# main-DESKTOP-L9L0IAD.net
KiCad netlist of a schematic drawn in Altium Designer
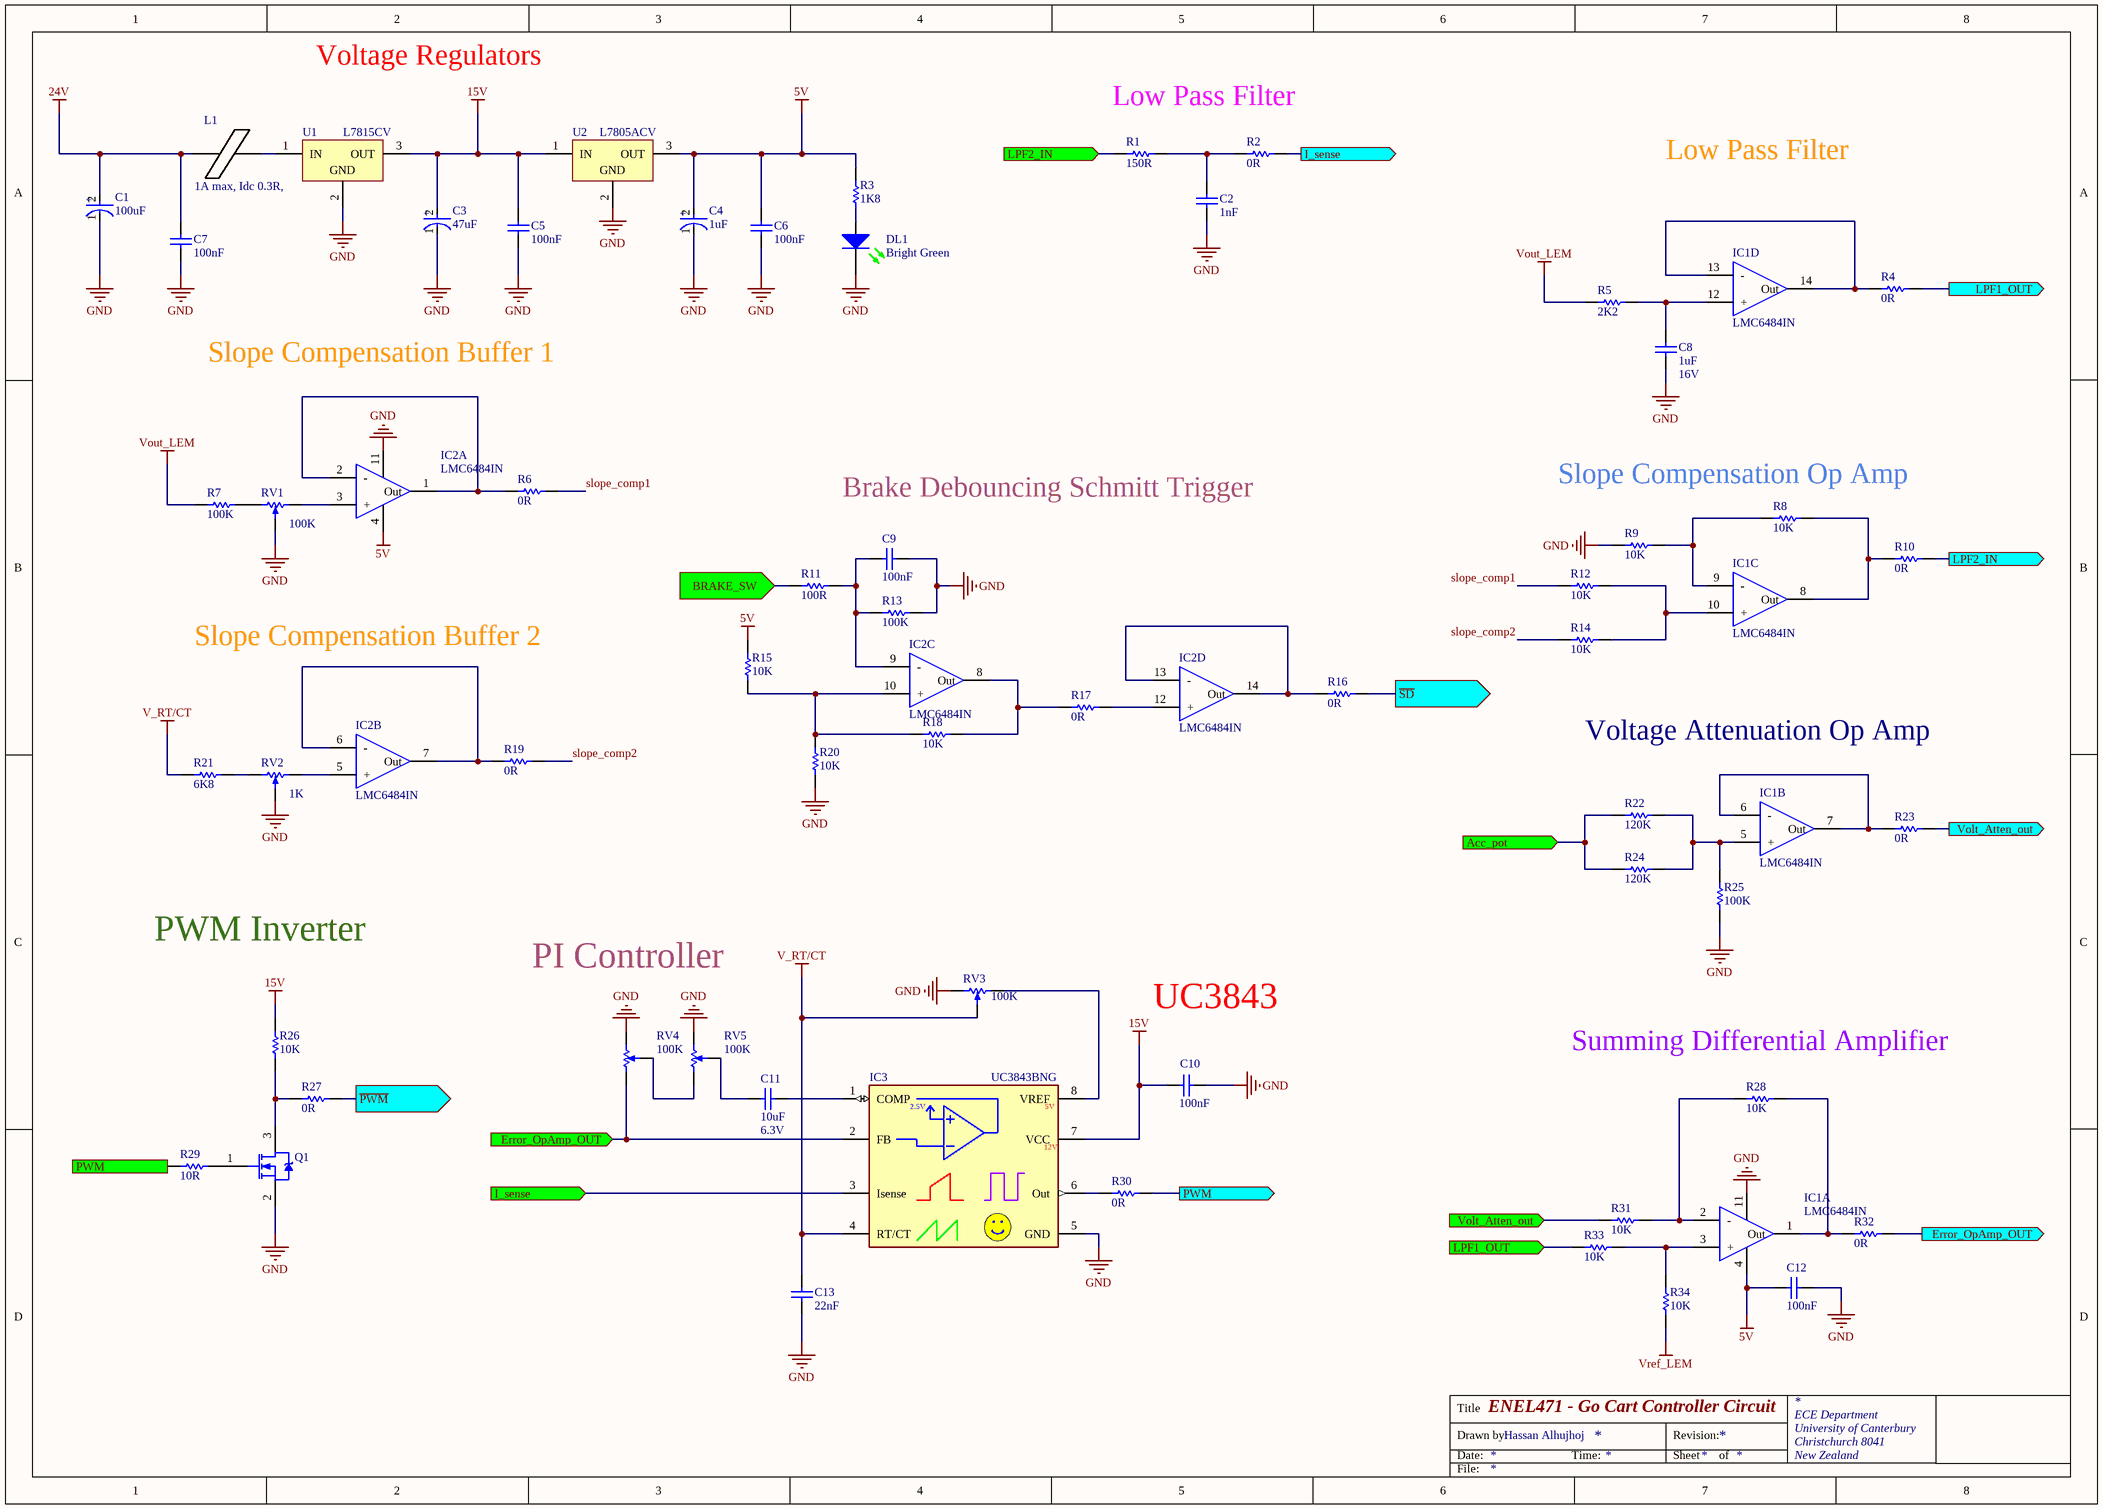
[diagram p0: main-DESKTOP-L9L0IAD.SchDoc]

(export (version "E")
  (design (tool "Eeschema 10.0.6"))
  (components
    (comp (ref "C1")
      (value "100uF")
      (footprint "FP-ESLGM-MFG")
      (description "CAP ALUM 100UF 20% 50V THRU HOLE. Part Number: ESL107M050AGMAA. Dia: 8mm.")
      (fields
        (field (name "TOLERANCE") "20%")
        (field (name "OCTOPART") "https://octopart.com/esl107m050agmaa-kemet-84758890")
      )
      (libsource (lib "Altium Content Vault") (part "a00bbbee19879c290e62620ae7e47b1"))
    )
    (comp (ref "C2")
      (value "1nF")
      (footprint "CAPC1608L")
      (description "CAP CER 1nF X7R +-10% 50V 0603")
      (libsource (lib "ECE AD19Components_19V1") (part "CC_1nF_0603"))
    )
    (comp (ref "C3")
      (value "47uF")
      (footprint "FP-ESLE3-MFG")
      (description "CAP ALUM 10UF 20% 100V THRU HOLE. Part Number: ESL106M100AE3AA. Dia: 6.3mm.")
      (fields (field (name "TOLERANCE") "20%") (field (name "MANUFACTURER PART NUMBER") "ESL106M100AE3AA"))
      (libsource (lib "Altium Content Vault") (part "cf48714ba7e38822c1575c7ec0b6d1f"))
    )
    (comp (ref "C4")
      (value "1uF")
      (footprint "FP-UPW1E220MDD-MFG")
      (description "CAP ALUM 22UF 20% 25V RADIAL. Part Number: UPW1E220MDD. Dia: 5mm.")
      (fields
        (field (name "OCTOPART") "https://octopart.com/upw1e220mdd-nichicon-202818")
        (field (name "TOLERANCE") "20%")
      )
      (libsource (lib "Altium Content Vault") (part "cf48714ba7e38822c1575c7ec0b6d1f"))
    )
    (comp (ref "C5")
      (value "100nF")
      (footprint "CAPC1608L")
      (description "CAP CER 100nF X7R +-10% 50V 0603")
      (libsource (lib "ECE AD19Components_19V1") (part "CC_100nF_0603"))
    )
    (comp (ref "C6")
      (value "100nF")
      (footprint "CAPC1608L")
      (description "CAP CER 100nF X7R +-10% 50V 0603")
      (libsource (lib "ECE AD19Components_19V1") (part "CC_100nF_0603"))
    )
    (comp (ref "C7")
      (value "100nF")
      (footprint "CAPC1608L")
      (description "CAP CER 100nF X7R +-10% 50V 0603")
      (libsource (lib "ECE AD19Components_19V1") (part "CC_100nF_0603"))
    )
    (comp (ref "C8")
      (value "1uF")
      (footprint "CAPC1608L")
      (description "CAP CER 1uF Y5V -20% +80% 16V 0603")
      (fields (field (name "MAX VOLTAGE") "16V"))
      (libsource (lib "ECE AD19Components_19V1") (part "CC_1uF_0603"))
    )
    (comp (ref "C9")
      (value "100nF")
      (footprint "CAPC1608L")
      (description "CAP CER 100nF X7R +-10% 50V 0603")
      (libsource (lib "ECE AD19Components_19V1") (part "CC_100nF_0603"))
    )
    (comp (ref "C10")
      (value "100nF")
      (footprint "CAPC1608L")
      (description "CAP CER 100nF X7R +-10% 50V 0603")
      (libsource (lib "ECE AD19Components_19V1") (part "CC_100nF_0603"))
    )
    (comp (ref "C11")
      (value "10uF")
      (footprint "CAPC1608L")
      (description "CAP CER 10UF X5R +-20% 6V3 0603")
      (fields (field (name "VOLTAGE - RATED") "6.3V"))
      (libsource (lib "ECE AD19Components_19V1") (part "CC_10uF_0603"))
    )
    (comp (ref "C12")
      (value "100nF")
      (footprint "CAPC1608L")
      (description "CAP CER 100nF X7R +-10% 50V 0603")
      (libsource (lib "ECE AD19Components_19V1") (part "CC_100nF_0603"))
    )
    (comp (ref "C13")
      (value "22nF")
      (footprint "CAPC1608L")
      (description "CAP CER 22nF X7R +-10% 50V 0603")
      (libsource (lib "ECE AD19Components_19V1") (part "CC_22nF_0603"))
    )
    (comp (ref "DL1")
      (value "Bright Green")
      (footprint "WL-SMCW0603")
      (description "LED Bright Green 40mcd 0603 SMD")
      (fields
        (field (name "MANUFACTURER") "WURTH ELEKTRONIK")
        (field (name "MANUFACTURER PART NUMBER") "150060VS75000")
        (field (name "LED COLOUR") "Bright Green")
      )
      (libsource (lib "ECE AD19Components_19V1") (part "DL_150060VS75000"))
    )
    (comp (ref "IC1")
      (value "LMC6484IN")
      (footprint "SamacSys:DIP794W56P254L1905H533Q14N")
      (description "Integrated Circuit")
      (fields (field (name "MOUSER PART NUMBER") "926-LMC6484IN"))
      (libsource (lib "SamacSys") (part "LMC6484IN"))
    )
    (comp (ref "IC2")
      (value "LMC6484IN")
      (footprint "SamacSys:DIP794W56P254L1905H533Q14N")
      (description "Integrated Circuit")
      (fields (field (name "MOUSER PART NUMBER") "926-LMC6484IN"))
      (libsource (lib "SamacSys") (part "LMC6484IN"))
    )
    (comp (ref "IC3")
      (value "UC3843BNG")
      (footprint "SamacSys:DIP794W56P254L959H533Q8B")
      (description "Integrated Circuit")
      (fields (field (name "MOUSER PART NUMBER") "863-UC3843BNG"))
      (libsource (lib "SamacSys") (part "UC3843BNG"))
    )
    (comp (ref "L1")
      (value "1A max, Idc 0.3R,")
      (footprint "INDC3216L")
      (description "Ferrite Bead, Rdc 0.3R, Z100MHZ 600R, Imax 1A, SMD 1206")
      (fields
        (field (name "MANUFACTURER") "FAIR-RITE")
        (field (name "MANUFACTURER PART NUMBER") "2512066017Y1")
      )
      (libsource (lib "ECE AD19Components_19V1") (part "IN_Ferrite-Bead"))
    )
    (comp (ref "Q1")
      (value "ZXM61N02FTA")
      (footprint "SOT23_L")
      (description "MOSFET N-CH 20V 1.7A SOT23-3")
      (fields (field (name "MANUFACTURER") "Diodes Inc"))
      (libsource (lib "ECE AD19Components_19V1") (part "TM_ZXM61N02FTA"))
    )
    (comp (ref "R1")
      (value "150R")
      (footprint "RESC1608L")
      (description "RES 150 OHM 1/10W 5% 0603 SMD")
      (libsource (lib "ECE AD19Components_19V1") (part "RS_150R"))
    )
    (comp (ref "R2")
      (value "0R")
      (footprint "RESC1608L")
      (description "RES 0.0 OHM 1/10W 5% 0603 SMD")
      (libsource (lib "ECE AD19Components_19V1") (part "RS_0R0"))
    )
    (comp (ref "R3")
      (value "1K8")
      (footprint "RESC1608L")
      (description "RES 1.8K OHM 1/10W 5% 0603 SMD")
      (libsource (lib "ECE AD19Components_19V1") (part "RS_1K8"))
    )
    (comp (ref "R4")
      (value "0R")
      (footprint "RESC1608L")
      (description "RES 0.0 OHM 1/10W 5% 0603 SMD")
      (libsource (lib "ECE AD19Components_19V1") (part "RS_0R0"))
    )
    (comp (ref "R5")
      (value "2K2")
      (footprint "RESC1608L")
      (description "RES 2.2K OHM 1/10W 5% 0603 SMD")
      (libsource (lib "ECE AD19Components_19V1") (part "RS_2K2"))
    )
    (comp (ref "R6")
      (value "0R")
      (footprint "RESC1608L")
      (description "RES 0.0 OHM 1/10W 5% 0603 SMD")
      (libsource (lib "ECE AD19Components_19V1") (part "RS_0R0"))
    )
    (comp (ref "R7")
      (value "100K")
      (footprint "RESC1608L")
      (description "RES 100K OHM 1/10W 5% 0603 SMD")
      (libsource (lib "ECE AD19Components_19V1") (part "RS_100K"))
    )
    (comp (ref "R8")
      (value "10K")
      (footprint "RESC1608L")
      (description "RES 10.0K OHM 1/10W 5% 0603 SMD")
      (libsource (lib "ECE AD19Components_19V1") (part "RS_10K"))
    )
    (comp (ref "R9")
      (value "10K")
      (footprint "RESC1608L")
      (description "RES 10.0K OHM 1/10W 5% 0603 SMD")
      (libsource (lib "ECE AD19Components_19V1") (part "RS_10K"))
    )
    (comp (ref "R10")
      (value "0R")
      (footprint "RESC1608L")
      (description "RES 0.0 OHM 1/10W 5% 0603 SMD")
      (libsource (lib "ECE AD19Components_19V1") (part "RS_0R0"))
    )
    (comp (ref "R11")
      (value "100R")
      (footprint "RESC1608L")
      (description "RES 100 OHM 1/10W 5% 0603 SMD")
      (libsource (lib "ECE AD19Components_19V1") (part "RS_100R"))
    )
    (comp (ref "R12")
      (value "10K")
      (footprint "RESC1608L")
      (description "RES 10.0K OHM 1/10W 5% 0603 SMD")
      (libsource (lib "ECE AD19Components_19V1") (part "RS_10K"))
    )
    (comp (ref "R13")
      (value "100K")
      (footprint "RESC1608L")
      (description "RES 100K OHM 1/10W 5% 0603 SMD")
      (libsource (lib "ECE AD19Components_19V1") (part "RS_100K"))
    )
    (comp (ref "R14")
      (value "10K")
      (footprint "RESC1608L")
      (description "RES 10.0K OHM 1/10W 5% 0603 SMD")
      (libsource (lib "ECE AD19Components_19V1") (part "RS_10K"))
    )
    (comp (ref "R15")
      (value "10K")
      (footprint "RESC1608L")
      (description "RES 10.0K OHM 1/10W 5% 0603 SMD")
      (libsource (lib "ECE AD19Components_19V1") (part "RS_10K"))
    )
    (comp (ref "R16")
      (value "0R")
      (footprint "RESC1608L")
      (description "RES 0.0 OHM 1/10W 5% 0603 SMD")
      (libsource (lib "ECE AD19Components_19V1") (part "RS_0R0"))
    )
    (comp (ref "R17")
      (value "0R")
      (footprint "RESC1608L")
      (description "RES 0.0 OHM 1/10W 5% 0603 SMD")
      (libsource (lib "ECE AD19Components_19V1") (part "RS_0R0"))
    )
    (comp (ref "R18")
      (value "10K")
      (footprint "RESC1608L")
      (description "RES 10.0K OHM 1/10W 5% 0603 SMD")
      (libsource (lib "ECE AD19Components_19V1") (part "RS_10K"))
    )
    (comp (ref "R19")
      (value "0R")
      (footprint "RESC1608L")
      (description "RES 0.0 OHM 1/10W 5% 0603 SMD")
      (libsource (lib "ECE AD19Components_19V1") (part "RS_0R0"))
    )
    (comp (ref "R20")
      (value "10K")
      (footprint "RESC1608L")
      (description "RES 10.0K OHM 1/10W 5% 0603 SMD")
      (libsource (lib "ECE AD19Components_19V1") (part "RS_10K"))
    )
    (comp (ref "R21")
      (value "6K8")
      (footprint "RESC1608L")
      (description "RES 6k8 OHM 1/10W 5% 0603 SMD")
      (libsource (lib "ECE AD19Components_19V1") (part "RS_6K8"))
    )
    (comp (ref "R22")
      (value "120K")
      (footprint "RESC1608L")
      (description "RES 120K OHM 1/10W 5% 0603 SMD")
      (libsource (lib "ECE AD19Components_19V1") (part "RS_120K"))
    )
    (comp (ref "R23")
      (value "0R")
      (footprint "RESC1608L")
      (description "RES 0.0 OHM 1/10W 5% 0603 SMD")
      (libsource (lib "ECE AD19Components_19V1") (part "RS_0R0"))
    )
    (comp (ref "R24")
      (value "120K")
      (footprint "RESC1608L")
      (description "RES 120K OHM 1/10W 5% 0603 SMD")
      (libsource (lib "ECE AD19Components_19V1") (part "RS_120K"))
    )
    (comp (ref "R25")
      (value "100K")
      (footprint "RESC1608L")
      (description "RES 100K OHM 1/10W 5% 0603 SMD")
      (libsource (lib "ECE AD19Components_19V1") (part "RS_100K"))
    )
    (comp (ref "R26")
      (value "10K")
      (footprint "RESC1608L")
      (description "RES 10.0K OHM 1/10W 5% 0603 SMD")
      (libsource (lib "ECE AD19Components_19V1") (part "RS_10K"))
    )
    (comp (ref "R27")
      (value "0R")
      (footprint "RESC1608L")
      (description "RES 0.0 OHM 1/10W 5% 0603 SMD")
      (libsource (lib "ECE AD19Components_19V1") (part "RS_0R0"))
    )
    (comp (ref "R28")
      (value "10K")
      (footprint "RESC1608L")
      (description "RES 10.0K OHM 1/10W 5% 0603 SMD")
      (libsource (lib "ECE AD19Components_19V1") (part "RS_10K"))
    )
    (comp (ref "R29")
      (value "10R")
      (footprint "RESC1608L")
      (description "RES 10 OHM 1/10W 5% 0603 SMD")
      (libsource (lib "ECE AD19Components_19V1") (part "RS_10R"))
    )
    (comp (ref "R30")
      (value "0R")
      (footprint "RESC1608L")
      (description "RES 0.0 OHM 1/10W 5% 0603 SMD")
      (libsource (lib "ECE AD19Components_19V1") (part "RS_0R0"))
    )
    (comp (ref "R31")
      (value "10K")
      (footprint "RESC1608L")
      (description "RES 10.0K OHM 1/10W 5% 0603 SMD")
      (libsource (lib "ECE AD19Components_19V1") (part "RS_10K"))
    )
    (comp (ref "R32")
      (value "0R")
      (footprint "RESC1608L")
      (description "RES 0.0 OHM 1/10W 5% 0603 SMD")
      (libsource (lib "ECE AD19Components_19V1") (part "RS_0R0"))
    )
    (comp (ref "R33")
      (value "10K")
      (footprint "RESC1608L")
      (description "RES 10.0K OHM 1/10W 5% 0603 SMD")
      (libsource (lib "ECE AD19Components_19V1") (part "RS_10K"))
    )
    (comp (ref "R34")
      (value "10K")
      (footprint "RESC1608L")
      (description "RES 10.0K OHM 1/10W 5% 0603 SMD")
      (libsource (lib "ECE AD19Components_19V1") (part "RS_10K"))
    )
    (comp (ref "RV1")
      (value "100K")
      (footprint "PVZ2A")
      (description "Trim Pot SMD 100K Murata PVZ2 Series SMD")
      (fields
        (field (name "MANUFACTURER") "MURATA")
        (field (name "MANUFACTURER PART NUMBER") "PVZ2A104C04B00")
      )
      (libsource (lib "ECE AD19Components_19V1") (part "RM_100K"))
    )
    (comp (ref "RV2")
      (value "1K")
      (footprint "PVZ2A")
      (description "Trim Pot SMD 1K Murata PVZ2 Series SMD")
      (fields
        (field (name "MANUFACTURER") "MURATA")
        (field (name "MANUFACTURER PART NUMBER") "PVZ2A102C04B00")
      )
      (libsource (lib "ECE AD19Components_19V1") (part "RM_1K"))
    )
    (comp (ref "RV3")
      (value "100K")
      (footprint "PVZ2A")
      (description "Trim Pot SMD 100K Murata PVZ2 Series SMD")
      (fields
        (field (name "MANUFACTURER") "MURATA")
        (field (name "MANUFACTURER PART NUMBER") "PVZ2A104C04B00")
      )
      (libsource (lib "ECE AD19Components_19V1") (part "RM_100K"))
    )
    (comp (ref "RV4")
      (value "100K")
      (footprint "PVZ2A")
      (description "Trim Pot SMD 100K Murata PVZ2 Series SMD")
      (fields
        (field (name "MANUFACTURER") "MURATA")
        (field (name "MANUFACTURER PART NUMBER") "PVZ2A104C04B00")
      )
      (libsource (lib "ECE AD19Components_19V1") (part "RM_100K"))
    )
    (comp (ref "RV5")
      (value "100K")
      (footprint "PVZ2A")
      (description "Trim Pot SMD 100K Murata PVZ2 Series SMD")
      (fields
        (field (name "MANUFACTURER") "MURATA")
        (field (name "MANUFACTURER PART NUMBER") "PVZ2A104C04B00")
      )
      (libsource (lib "ECE AD19Components_19V1") (part "RM_100K"))
    )
    (comp (ref "U1")
      (value "L7815CV")
      (footprint "TO220")
      (description "Positive Voltage Regulator, 15V, 3-Pin TO-220")
      (libsource (lib "Altium Content Vault") (part "PM-REG-L4940-SIL3"))
    )
    (comp (ref "U2")
      (value "L7805ACV")
      (footprint "TO220")
      (description "Positive Voltage Regulator, 5V, 3-Pin TO-220")
      (libsource (lib "Altium Content Vault") (part "PM-REG-L4940-SIL3"))
    )
  )
  (nets
    (net (code "1") (name "/Acc_pot") (class "Default")
      (node (ref "R22") (pin "2") (pinfunction "2_2") (pintype "passive"))
      (node (ref "R24") (pin "1") (pinfunction "1_1") (pintype "passive"))
    )
    (net (code "2") (name "/BRAKE_SW") (class "Default")
      (node (ref "R11") (pin "1") (pinfunction "1_1") (pintype "passive"))
    )
    (net (code "3") (name "/Error_OpAmp_OUT") (class "Default")
      (node (ref "IC3") (pin "2") (pinfunction "FB_2") (pintype "passive"))
      (node (ref "R32") (pin "2") (pinfunction "2_2") (pintype "passive"))
      (node (ref "RV4") (pin "3") (pinfunction "-_3") (pintype "passive"))
    )
    (net (code "4") (name "/I_sense") (class "Default")
      (node (ref "IC3") (pin "3") (pinfunction "Isense_3") (pintype "passive"))
      (node (ref "R2") (pin "2") (pinfunction "2_2") (pintype "passive"))
    )
    (net (code "5") (name "/LPF1_OUT") (class "Default")
      (node (ref "R33") (pin "1") (pinfunction "1_1") (pintype "passive"))
      (node (ref "R4") (pin "2") (pinfunction "2_2") (pintype "passive"))
    )
    (net (code "6") (name "/LPF2_IN") (class "Default")
      (node (ref "R1") (pin "1") (pinfunction "1_1") (pintype "passive"))
      (node (ref "R10") (pin "2") (pinfunction "2_2") (pintype "passive"))
    )
    (net (code "7") (name "/PWM") (class "Default")
      (node (ref "R29") (pin "1") (pinfunction "1_1") (pintype "passive"))
      (node (ref "R30") (pin "2") (pinfunction "2_2") (pintype "passive"))
    )
    (net (code "8") (name "/Volt_Atten_out") (class "Default")
      (node (ref "R23") (pin "2") (pinfunction "2_2") (pintype "passive"))
      (node (ref "R31") (pin "1") (pinfunction "1_1") (pintype "passive"))
    )
    (net (code "9") (name "/slope_comp1") (class "Default")
      (node (ref "R12") (pin "1") (pinfunction "1_1") (pintype "passive"))
      (node (ref "R6") (pin "2") (pinfunction "2_2") (pintype "passive"))
    )
    (net (code "10") (name "/slope_comp2") (class "Default")
      (node (ref "R14") (pin "1") (pinfunction "1_1") (pintype "passive"))
      (node (ref "R19") (pin "2") (pinfunction "2_2") (pintype "passive"))
    )
    (net (code "11") (name "/~{PWM}") (class "Default")
      (node (ref "R27") (pin "2") (pinfunction "2_2") (pintype "passive"))
    )
    (net (code "12") (name "/~{SD}") (class "Default")
      (node (ref "R16") (pin "2") (pinfunction "2_2") (pintype "passive"))
    )
    (net (code "13") (name "5V") (class "Default")
      (node (ref "C12") (pin "1") (pinfunction "1_1") (pintype "passive"))
      (node (ref "C4") (pin "2") (pinfunction "A_2") (pintype "passive"))
      (node (ref "C6") (pin "1") (pinfunction "1_1") (pintype "passive"))
      (node (ref "IC1") (pin "4") (pinfunction "Vcc_4") (pintype "power_in"))
      (node (ref "IC2") (pin "4") (pinfunction "Vcc_4") (pintype "power_in"))
      (node (ref "R15") (pin "2") (pinfunction "2_2") (pintype "passive"))
      (node (ref "R3") (pin "1") (pinfunction "1_1") (pintype "passive"))
      (node (ref "U2") (pin "3") (pinfunction "OUT_3") (pintype "power_in"))
    )
    (net (code "14") (name "15V") (class "Default")
      (node (ref "C10") (pin "1") (pinfunction "1_1") (pintype "passive"))
      (node (ref "C3") (pin "2") (pinfunction "A_2") (pintype "passive"))
      (node (ref "C5") (pin "1") (pinfunction "1_1") (pintype "passive"))
      (node (ref "IC3") (pin "7") (pinfunction "VCC_7") (pintype "power_in"))
      (node (ref "R26") (pin "2") (pinfunction "2_2") (pintype "passive"))
      (node (ref "U1") (pin "3") (pinfunction "OUT_3") (pintype "power_in"))
      (node (ref "U2") (pin "1") (pinfunction "IN_1") (pintype "power_in"))
    )
    (net (code "15") (name "24V") (class "Default")
      (node (ref "C1") (pin "2") (pinfunction "A_2") (pintype "passive"))
      (node (ref "C7") (pin "1") (pinfunction "1_1") (pintype "passive"))
      (node (ref "L1") (pin "1") (pinfunction "1_1") (pintype "passive"))
    )
    (net (code "16") (name "GND") (class "Default")
      (node (ref "C1") (pin "1") (pinfunction "C_1") (pintype "passive"))
      (node (ref "C10") (pin "2") (pinfunction "2_2") (pintype "passive"))
      (node (ref "C12") (pin "2") (pinfunction "2_2") (pintype "passive"))
      (node (ref "C13") (pin "2") (pinfunction "2_2") (pintype "passive"))
      (node (ref "C2") (pin "1") (pinfunction "1_1") (pintype "passive"))
      (node (ref "C3") (pin "1") (pinfunction "C_1") (pintype "passive"))
      (node (ref "C4") (pin "1") (pinfunction "C_1") (pintype "passive"))
      (node (ref "C5") (pin "2") (pinfunction "2_2") (pintype "passive"))
      (node (ref "C6") (pin "2") (pinfunction "2_2") (pintype "passive"))
      (node (ref "C7") (pin "2") (pinfunction "2_2") (pintype "passive"))
      (node (ref "C8") (pin "1") (pinfunction "1_1") (pintype "passive"))
      (node (ref "C9") (pin "2") (pinfunction "2_2") (pintype "passive"))
      (node (ref "DL1") (pin "1") (pinfunction "K_1") (pintype "passive"))
      (node (ref "IC1") (pin "11") (pinfunction "-Vcc_11") (pintype "power_in"))
      (node (ref "IC2") (pin "11") (pinfunction "-Vcc_11") (pintype "power_in"))
      (node (ref "IC3") (pin "5") (pinfunction "GND_5") (pintype "power_in"))
      (node (ref "Q1") (pin "2") (pinfunction "2_2") (pintype "passive"))
      (node (ref "R13") (pin "2") (pinfunction "2_2") (pintype "passive"))
      (node (ref "R20") (pin "1") (pinfunction "1_1") (pintype "passive"))
      (node (ref "R25") (pin "1") (pinfunction "1_1") (pintype "passive"))
      (node (ref "R9") (pin "1") (pinfunction "1_1") (pintype "passive"))
      (node (ref "RV1") (pin "2") (pinfunction "W_2") (pintype "passive"))
      (node (ref "RV2") (pin "2") (pinfunction "W_2") (pintype "passive"))
      (node (ref "RV3") (pin "3") (pinfunction "-_3") (pintype "passive"))
      (node (ref "RV4") (pin "1") (pinfunction "1_1") (pintype "passive"))
      (node (ref "RV5") (pin "1") (pinfunction "1_1") (pintype "passive"))
      (node (ref "U1") (pin "2") (pinfunction "GND_2") (pintype "power_in"))
      (node (ref "U2") (pin "2") (pinfunction "GND_2") (pintype "power_in"))
    )
    (net (code "17") (name "Net-(C2-Pad2)") (class "Default")
      (node (ref "C2") (pin "2") (pinfunction "2_2") (pintype "passive"))
      (node (ref "R1") (pin "2") (pinfunction "2_2") (pintype "passive"))
      (node (ref "R2") (pin "1") (pinfunction "1_1") (pintype "passive"))
    )
    (net (code "18") (name "Net-(DL1-A)") (class "Default")
      (node (ref "DL1") (pin "2") (pinfunction "A_2") (pintype "passive"))
      (node (ref "R3") (pin "2") (pinfunction "2_2") (pintype "passive"))
    )
    (net (code "19") (name "Net-(IC1A-+)") (class "Default")
      (node (ref "IC1") (pin "3") (pinfunction "+_3") (pintype "passive"))
      (node (ref "R33") (pin "2") (pinfunction "2_2") (pintype "passive"))
      (node (ref "R34") (pin "2") (pinfunction "2_2") (pintype "passive"))
    )
    (net (code "20") (name "Net-(IC1A--)") (class "Default")
      (node (ref "IC1") (pin "2") (pinfunction "-_2") (pintype "passive"))
      (node (ref "R28") (pin "1") (pinfunction "1_1") (pintype "passive"))
      (node (ref "R31") (pin "2") (pinfunction "2_2") (pintype "passive"))
    )
    (net (code "21") (name "Net-(IC1A-Out)") (class "Default")
      (node (ref "IC1") (pin "1") (pinfunction "Out_1") (pintype "passive"))
      (node (ref "R28") (pin "2") (pinfunction "2_2") (pintype "passive"))
      (node (ref "R32") (pin "1") (pinfunction "1_1") (pintype "passive"))
    )
    (net (code "22") (name "Net-(IC1B-+)") (class "Default")
      (node (ref "IC1") (pin "5") (pinfunction "+_5") (pintype "passive"))
      (node (ref "R22") (pin "1") (pinfunction "1_1") (pintype "passive"))
      (node (ref "R24") (pin "2") (pinfunction "2_2") (pintype "passive"))
      (node (ref "R25") (pin "2") (pinfunction "2_2") (pintype "passive"))
    )
    (net (code "23") (name "Net-(IC1B--)") (class "Default")
      (node (ref "IC1") (pin "6") (pinfunction "-_6") (pintype "passive"))
      (node (ref "IC1") (pin "7") (pinfunction "Out_7") (pintype "passive"))
      (node (ref "R23") (pin "1") (pinfunction "1_1") (pintype "passive"))
    )
    (net (code "24") (name "Net-(IC1C-+)") (class "Default")
      (node (ref "IC1") (pin "10") (pinfunction "+_10") (pintype "passive"))
      (node (ref "R12") (pin "2") (pinfunction "2_2") (pintype "passive"))
      (node (ref "R14") (pin "2") (pinfunction "2_2") (pintype "passive"))
    )
    (net (code "25") (name "Net-(IC1C--)") (class "Default")
      (node (ref "IC1") (pin "9") (pinfunction "-_9") (pintype "passive"))
      (node (ref "R8") (pin "1") (pinfunction "1_1") (pintype "passive"))
      (node (ref "R9") (pin "2") (pinfunction "2_2") (pintype "passive"))
    )
    (net (code "26") (name "Net-(IC1C-Out)") (class "Default")
      (node (ref "IC1") (pin "8") (pinfunction "Out_8") (pintype "passive"))
      (node (ref "R10") (pin "1") (pinfunction "1_1") (pintype "passive"))
      (node (ref "R8") (pin "2") (pinfunction "2_2") (pintype "passive"))
    )
    (net (code "27") (name "Net-(IC1D-+)") (class "Default")
      (node (ref "C8") (pin "2") (pinfunction "2_2") (pintype "passive"))
      (node (ref "IC1") (pin "12") (pinfunction "+_12") (pintype "passive"))
      (node (ref "R5") (pin "1") (pinfunction "1_1") (pintype "passive"))
    )
    (net (code "28") (name "Net-(IC1D--)") (class "Default")
      (node (ref "IC1") (pin "13") (pinfunction "-_13") (pintype "passive"))
      (node (ref "IC1") (pin "14") (pinfunction "Out_14") (pintype "passive"))
      (node (ref "R4") (pin "1") (pinfunction "1_1") (pintype "passive"))
    )
    (net (code "29") (name "Net-(IC2A-+)") (class "Default")
      (node (ref "IC2") (pin "3") (pinfunction "+_3") (pintype "passive"))
      (node (ref "RV1") (pin "1") (pinfunction "1_1") (pintype "passive"))
    )
    (net (code "30") (name "Net-(IC2A--)") (class "Default")
      (node (ref "IC2") (pin "1") (pinfunction "Out_1") (pintype "passive"))
      (node (ref "IC2") (pin "2") (pinfunction "-_2") (pintype "passive"))
      (node (ref "R6") (pin "1") (pinfunction "1_1") (pintype "passive"))
    )
    (net (code "31") (name "Net-(IC2B-+)") (class "Default")
      (node (ref "IC2") (pin "5") (pinfunction "+_5") (pintype "passive"))
      (node (ref "RV2") (pin "1") (pinfunction "1_1") (pintype "passive"))
    )
    (net (code "32") (name "Net-(IC2B--)") (class "Default")
      (node (ref "IC2") (pin "6") (pinfunction "-_6") (pintype "passive"))
      (node (ref "IC2") (pin "7") (pinfunction "Out_7") (pintype "passive"))
      (node (ref "R19") (pin "1") (pinfunction "1_1") (pintype "passive"))
    )
    (net (code "33") (name "Net-(IC2C-+)") (class "Default")
      (node (ref "IC2") (pin "10") (pinfunction "+_10") (pintype "passive"))
      (node (ref "R15") (pin "1") (pinfunction "1_1") (pintype "passive"))
      (node (ref "R18") (pin "1") (pinfunction "1_1") (pintype "passive"))
      (node (ref "R20") (pin "2") (pinfunction "2_2") (pintype "passive"))
    )
    (net (code "34") (name "Net-(IC2C--)") (class "Default")
      (node (ref "C9") (pin "1") (pinfunction "1_1") (pintype "passive"))
      (node (ref "IC2") (pin "9") (pinfunction "-_9") (pintype "passive"))
      (node (ref "R11") (pin "2") (pinfunction "2_2") (pintype "passive"))
      (node (ref "R13") (pin "1") (pinfunction "1_1") (pintype "passive"))
    )
    (net (code "35") (name "Net-(IC2C-Out)") (class "Default")
      (node (ref "IC2") (pin "8") (pinfunction "Out_8") (pintype "passive"))
      (node (ref "R17") (pin "1") (pinfunction "1_1") (pintype "passive"))
      (node (ref "R18") (pin "2") (pinfunction "2_2") (pintype "passive"))
    )
    (net (code "36") (name "Net-(IC2D-+)") (class "Default")
      (node (ref "IC2") (pin "12") (pinfunction "+_12") (pintype "passive"))
      (node (ref "R17") (pin "2") (pinfunction "2_2") (pintype "passive"))
    )
    (net (code "37") (name "Net-(IC2D--)") (class "Default")
      (node (ref "IC2") (pin "13") (pinfunction "-_13") (pintype "passive"))
      (node (ref "IC2") (pin "14") (pinfunction "Out_14") (pintype "passive"))
      (node (ref "R16") (pin "1") (pinfunction "1_1") (pintype "passive"))
    )
    (net (code "38") (name "Net-(IC3-COMP)") (class "Default")
      (node (ref "C11") (pin "1") (pinfunction "1_1") (pintype "passive"))
      (node (ref "IC3") (pin "1") (pinfunction "COMP_1") (pintype "bidirectional"))
    )
    (net (code "39") (name "Net-(IC3-Out)") (class "Default")
      (node (ref "IC3") (pin "6") (pinfunction "Out_6") (pintype "output"))
      (node (ref "R30") (pin "1") (pinfunction "1_1") (pintype "passive"))
    )
    (net (code "40") (name "Net-(IC3-VREF)") (class "Default")
      (node (ref "IC3") (pin "8") (pinfunction "VREF_8") (pintype "power_in"))
      (node (ref "RV3") (pin "1") (pinfunction "1_1") (pintype "passive"))
    )
    (net (code "41") (name "Net-(Q1-Pad1)") (class "Default")
      (node (ref "Q1") (pin "1") (pinfunction "1_1") (pintype "passive"))
      (node (ref "R29") (pin "2") (pinfunction "2_2") (pintype "passive"))
    )
    (net (code "42") (name "Net-(Q1-Pad3)") (class "Default")
      (node (ref "Q1") (pin "3") (pinfunction "3_3") (pintype "passive"))
      (node (ref "R26") (pin "1") (pinfunction "1_1") (pintype "passive"))
      (node (ref "R27") (pin "1") (pinfunction "1_1") (pintype "passive"))
    )
    (net (code "43") (name "Net-(RV1--)") (class "Default")
      (node (ref "R7") (pin "2") (pinfunction "2_2") (pintype "passive"))
      (node (ref "RV1") (pin "3") (pinfunction "-_3") (pintype "passive"))
    )
    (net (code "44") (name "Net-(RV2--)") (class "Default")
      (node (ref "R21") (pin "2") (pinfunction "2_2") (pintype "passive"))
      (node (ref "RV2") (pin "3") (pinfunction "-_3") (pintype "passive"))
    )
    (net (code "45") (name "Net-(RV4-W)") (class "Default")
      (node (ref "RV4") (pin "2") (pinfunction "W_2") (pintype "passive"))
      (node (ref "RV5") (pin "3") (pinfunction "-_3") (pintype "passive"))
    )
    (net (code "46") (name "Net-(RV5-W)") (class "Default")
      (node (ref "C11") (pin "2") (pinfunction "2_2") (pintype "passive"))
      (node (ref "RV5") (pin "2") (pinfunction "W_2") (pintype "passive"))
    )
    (net (code "47") (name "Net-(U1-IN)") (class "Default")
      (node (ref "L1") (pin "2") (pinfunction "2_2") (pintype "passive"))
      (node (ref "U1") (pin "1") (pinfunction "IN_1") (pintype "power_in"))
    )
    (net (code "48") (name "V_RT{slash}CT") (class "Default")
      (node (ref "C13") (pin "1") (pinfunction "1_1") (pintype "passive"))
      (node (ref "IC3") (pin "4") (pinfunction "RT/CT_4") (pintype "passive"))
      (node (ref "R21") (pin "1") (pinfunction "1_1") (pintype "passive"))
      (node (ref "RV3") (pin "2") (pinfunction "W_2") (pintype "passive"))
    )
    (net (code "49") (name "Vout_LEM") (class "Default")
      (node (ref "R5") (pin "2") (pinfunction "2_2") (pintype "passive"))
      (node (ref "R7") (pin "1") (pinfunction "1_1") (pintype "passive"))
    )
    (net (code "50") (name "Vref_LEM") (class "Default")
      (node (ref "R34") (pin "1") (pinfunction "1_1") (pintype "passive"))
    )
  )
)
